# DSKY.net
KiCad netlist of a schematic drawn in EAGLE
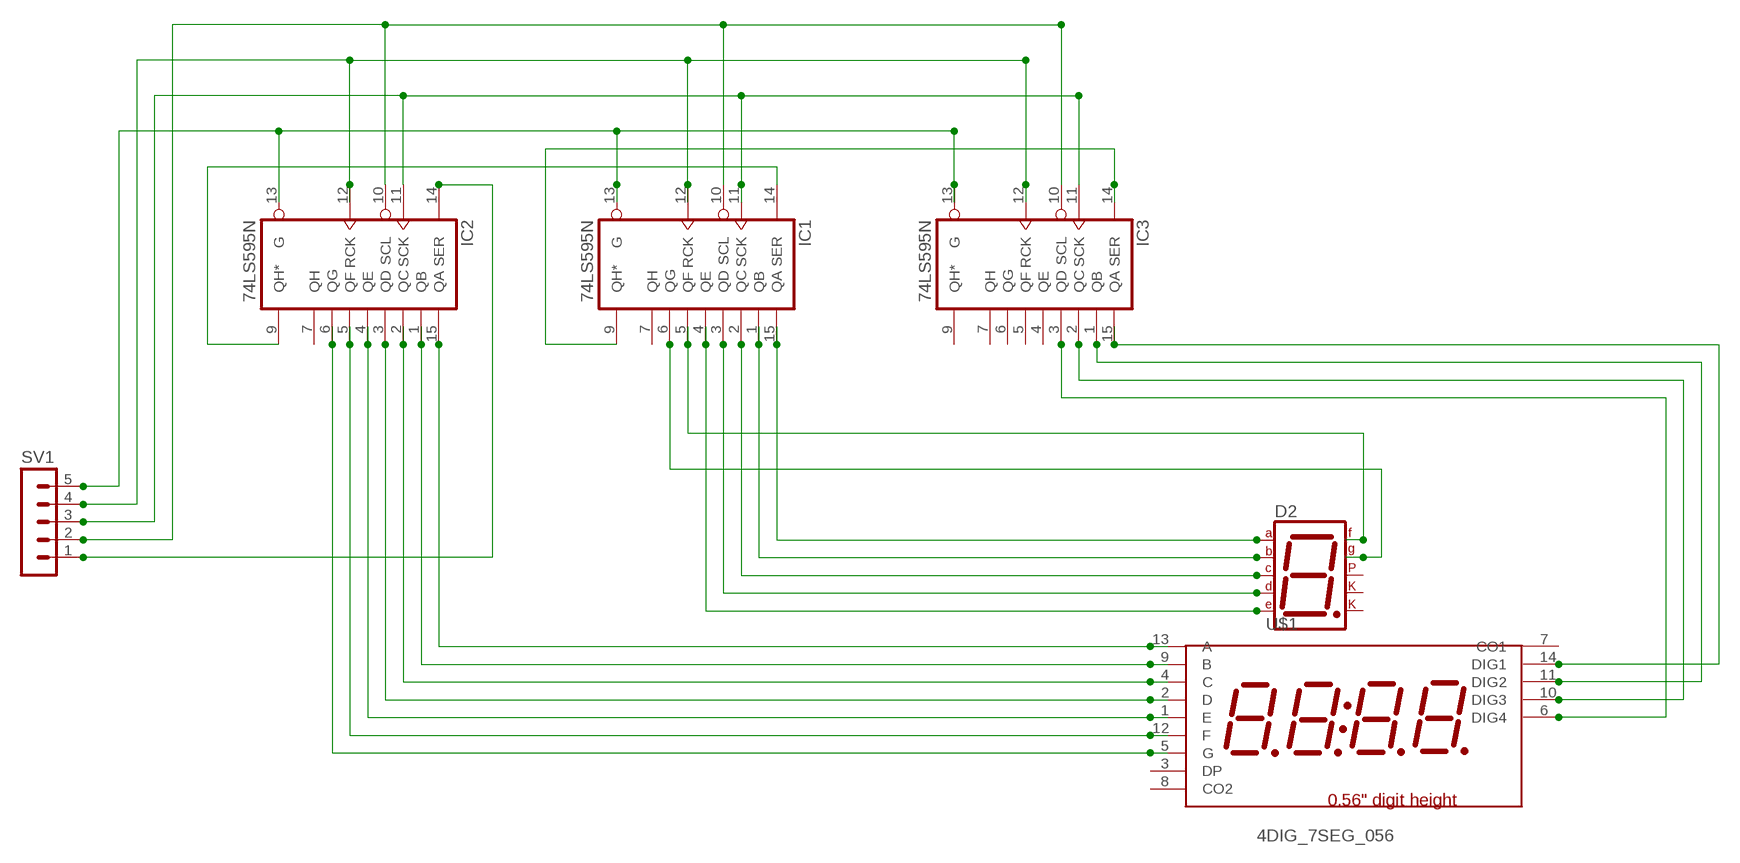
[diagram p0: schematic, sheet 1]

(export (version "E")
  (design (tool "Eeschema 10.0.6"))
  (components
    (comp (ref "D2")
      (value "7SEG-CK")
      (footprint "eagle-import:7SEG-13")
      (libsource (lib "eagle-import") (part "7SEG-CK"))
    )
    (comp (ref "IC1")
      (value "74LS595N")
      (footprint "eagle-import:DIL16")
      (libsource (lib "eagle-import") (part "74595NLS"))
    )
    (comp (ref "IC2")
      (value "74LS595N")
      (footprint "eagle-import:DIL16")
      (libsource (lib "eagle-import") (part "74595NLS"))
    )
    (comp (ref "IC3")
      (value "74LS595N")
      (footprint "eagle-import:DIL16")
      (libsource (lib "eagle-import") (part "74595NLS"))
    )
    (comp (ref "SV1")
      (value "MA05-1")
      (footprint "eagle-import:MA05-1")
      (libsource (lib "eagle-import") (part "MA05-1"))
    )
    (comp (ref "U$1")
      (value "4DIG_7SEG_056")
      (footprint "eagle-import:4DIG_7SEG_056")
      (libsource (lib "eagle-import") (part "4DIG_7SEG_056"))
    )
  )
  (nets
    (net (code "1") (name "Net-(D2-A)") (class "Default")
      (node (ref "D2") (pin "7") (pinfunction "A_7") (pintype "passive"))
      (node (ref "IC1") (pin "15") (pinfunction "QA_15") (pintype "tri_state"))
    )
    (net (code "2") (name "Net-(D2-B)") (class "Default")
      (node (ref "D2") (pin "6") (pinfunction "B_6") (pintype "passive"))
      (node (ref "IC1") (pin "1") (pinfunction "QB_1") (pintype "tri_state"))
    )
    (net (code "3") (name "Net-(D2-C)") (class "Default")
      (node (ref "D2") (pin "4") (pinfunction "C_4") (pintype "passive"))
      (node (ref "IC1") (pin "2") (pinfunction "QC_2") (pintype "tri_state"))
    )
    (net (code "4") (name "Net-(D2-D)") (class "Default")
      (node (ref "D2") (pin "2") (pinfunction "D_2") (pintype "passive"))
      (node (ref "IC1") (pin "3") (pinfunction "QD_3") (pintype "tri_state"))
    )
    (net (code "5") (name "Net-(D2-E)") (class "Default")
      (node (ref "D2") (pin "1") (pinfunction "E_1") (pintype "passive"))
      (node (ref "IC1") (pin "4") (pinfunction "QE_4") (pintype "tri_state"))
    )
    (net (code "6") (name "Net-(D2-F)") (class "Default")
      (node (ref "D2") (pin "9") (pinfunction "F_9") (pintype "passive"))
      (node (ref "IC1") (pin "5") (pinfunction "QF_5") (pintype "tri_state"))
    )
    (net (code "7") (name "Net-(D2-G)") (class "Default")
      (node (ref "D2") (pin "10") (pinfunction "G_10") (pintype "passive"))
      (node (ref "IC1") (pin "6") (pinfunction "QG_6") (pintype "tri_state"))
    )
    (net (code "8") (name "Net-(IC1A-G)") (class "Default")
      (node (ref "IC1") (pin "13") (pinfunction "G_13") (pintype "input"))
      (node (ref "IC2") (pin "13") (pinfunction "G_13") (pintype "input"))
      (node (ref "IC3") (pin "13") (pinfunction "G_13") (pintype "input"))
      (node (ref "SV1") (pin "5") (pinfunction "5_5") (pintype "passive"))
    )
    (net (code "9") (name "Net-(IC1A-QH*)") (class "Default")
      (node (ref "IC1") (pin "9") (pinfunction "QH*_9") (pintype "tri_state"))
      (node (ref "IC3") (pin "14") (pinfunction "SER_14") (pintype "input"))
    )
    (net (code "10") (name "Net-(IC1A-RCK)") (class "Default")
      (node (ref "IC1") (pin "12") (pinfunction "RCK_12") (pintype "input"))
      (node (ref "IC2") (pin "12") (pinfunction "RCK_12") (pintype "input"))
      (node (ref "IC3") (pin "12") (pinfunction "RCK_12") (pintype "input"))
      (node (ref "SV1") (pin "4") (pinfunction "4_4") (pintype "passive"))
    )
    (net (code "11") (name "Net-(IC1A-SCK)") (class "Default")
      (node (ref "IC1") (pin "11") (pinfunction "SCK_11") (pintype "input"))
      (node (ref "IC2") (pin "11") (pinfunction "SCK_11") (pintype "input"))
      (node (ref "IC3") (pin "11") (pinfunction "SCK_11") (pintype "input"))
      (node (ref "SV1") (pin "3") (pinfunction "3_3") (pintype "passive"))
    )
    (net (code "12") (name "Net-(IC1A-SCL)") (class "Default")
      (node (ref "IC1") (pin "10") (pinfunction "SCL_10") (pintype "input"))
      (node (ref "IC2") (pin "10") (pinfunction "SCL_10") (pintype "input"))
      (node (ref "IC3") (pin "10") (pinfunction "SCL_10") (pintype "input"))
      (node (ref "SV1") (pin "2") (pinfunction "2_2") (pintype "passive"))
    )
    (net (code "13") (name "Net-(IC1A-SER)") (class "Default")
      (node (ref "IC1") (pin "14") (pinfunction "SER_14") (pintype "input"))
      (node (ref "IC2") (pin "9") (pinfunction "QH*_9") (pintype "tri_state"))
    )
    (net (code "14") (name "Net-(IC2A-QA)") (class "Default")
      (node (ref "IC2") (pin "15") (pinfunction "QA_15") (pintype "tri_state"))
      (node (ref "U$1") (pin "13") (pinfunction "A_13") (pintype "bidirectional"))
    )
    (net (code "15") (name "Net-(IC2A-QB)") (class "Default")
      (node (ref "IC2") (pin "1") (pinfunction "QB_1") (pintype "tri_state"))
      (node (ref "U$1") (pin "9") (pinfunction "B_9") (pintype "bidirectional"))
    )
    (net (code "16") (name "Net-(IC2A-QC)") (class "Default")
      (node (ref "IC2") (pin "2") (pinfunction "QC_2") (pintype "tri_state"))
      (node (ref "U$1") (pin "4") (pinfunction "C_4") (pintype "bidirectional"))
    )
    (net (code "17") (name "Net-(IC2A-QD)") (class "Default")
      (node (ref "IC2") (pin "3") (pinfunction "QD_3") (pintype "tri_state"))
      (node (ref "U$1") (pin "2") (pinfunction "D_2") (pintype "bidirectional"))
    )
    (net (code "18") (name "Net-(IC2A-QE)") (class "Default")
      (node (ref "IC2") (pin "4") (pinfunction "QE_4") (pintype "tri_state"))
      (node (ref "U$1") (pin "1") (pinfunction "E_1") (pintype "bidirectional"))
    )
    (net (code "19") (name "Net-(IC2A-QF)") (class "Default")
      (node (ref "IC2") (pin "5") (pinfunction "QF_5") (pintype "tri_state"))
      (node (ref "U$1") (pin "12") (pinfunction "F_12") (pintype "bidirectional"))
    )
    (net (code "20") (name "Net-(IC2A-QG)") (class "Default")
      (node (ref "IC2") (pin "6") (pinfunction "QG_6") (pintype "tri_state"))
      (node (ref "U$1") (pin "5") (pinfunction "G_5") (pintype "bidirectional"))
    )
    (net (code "21") (name "Net-(IC2A-SER)") (class "Default")
      (node (ref "IC2") (pin "14") (pinfunction "SER_14") (pintype "input"))
      (node (ref "SV1") (pin "1") (pinfunction "1_1") (pintype "passive"))
    )
    (net (code "22") (name "Net-(IC3A-QA)") (class "Default")
      (node (ref "IC3") (pin "15") (pinfunction "QA_15") (pintype "tri_state"))
      (node (ref "U$1") (pin "14") (pinfunction "DIG1_14") (pintype "bidirectional"))
    )
    (net (code "23") (name "Net-(IC3A-QB)") (class "Default")
      (node (ref "IC3") (pin "1") (pinfunction "QB_1") (pintype "tri_state"))
      (node (ref "U$1") (pin "11") (pinfunction "DIG2_11") (pintype "bidirectional"))
    )
    (net (code "24") (name "Net-(IC3A-QC)") (class "Default")
      (node (ref "IC3") (pin "2") (pinfunction "QC_2") (pintype "tri_state"))
      (node (ref "U$1") (pin "10") (pinfunction "DIG3_10") (pintype "bidirectional"))
    )
    (net (code "25") (name "Net-(IC3A-QD)") (class "Default")
      (node (ref "IC3") (pin "3") (pinfunction "QD_3") (pintype "tri_state"))
      (node (ref "U$1") (pin "6") (pinfunction "DIG4_6") (pintype "bidirectional"))
    )
    (net (code "26") (name "unconnected-(D2-CK1-Pad3)") (class "Default")
      (node (ref "D2") (pin "3") (pinfunction "CK1_3") (pintype "passive"))
    )
    (net (code "27") (name "unconnected-(D2-CK2-Pad8)") (class "Default")
      (node (ref "D2") (pin "8") (pinfunction "CK2_8") (pintype "passive"))
    )
    (net (code "28") (name "unconnected-(D2-DP-Pad5)") (class "Default")
      (node (ref "D2") (pin "5") (pinfunction "DP_5") (pintype "passive"))
    )
    (net (code "29") (name "unconnected-(IC1A-QH-Pad7)") (class "Default")
      (node (ref "IC1") (pin "7") (pinfunction "QH_7") (pintype "tri_state"))
    )
    (net (code "30") (name "unconnected-(IC2A-QH-Pad7)") (class "Default")
      (node (ref "IC2") (pin "7") (pinfunction "QH_7") (pintype "tri_state"))
    )
    (net (code "31") (name "unconnected-(IC3A-QE-Pad4)") (class "Default")
      (node (ref "IC3") (pin "4") (pinfunction "QE_4") (pintype "tri_state"))
    )
    (net (code "32") (name "unconnected-(IC3A-QF-Pad5)") (class "Default")
      (node (ref "IC3") (pin "5") (pinfunction "QF_5") (pintype "tri_state"))
    )
    (net (code "33") (name "unconnected-(IC3A-QG-Pad6)") (class "Default")
      (node (ref "IC3") (pin "6") (pinfunction "QG_6") (pintype "tri_state"))
    )
    (net (code "34") (name "unconnected-(IC3A-QH*-Pad9)") (class "Default")
      (node (ref "IC3") (pin "9") (pinfunction "QH*_9") (pintype "tri_state"))
    )
    (net (code "35") (name "unconnected-(IC3A-QH-Pad7)") (class "Default")
      (node (ref "IC3") (pin "7") (pinfunction "QH_7") (pintype "tri_state"))
    )
    (net (code "36") (name "unconnected-(U$1-CO1-Pad7)") (class "Default")
      (node (ref "U$1") (pin "7") (pinfunction "CO1_7") (pintype "bidirectional"))
    )
    (net (code "37") (name "unconnected-(U$1-CO2-Pad8)") (class "Default")
      (node (ref "U$1") (pin "8") (pinfunction "CO2_8") (pintype "bidirectional"))
    )
    (net (code "38") (name "unconnected-(U$1-DP-Pad3)") (class "Default")
      (node (ref "U$1") (pin "3") (pinfunction "DP_3") (pintype "bidirectional"))
    )
  )
)
